# Board.net
KiCad netlist of a schematic drawn in EAGLE
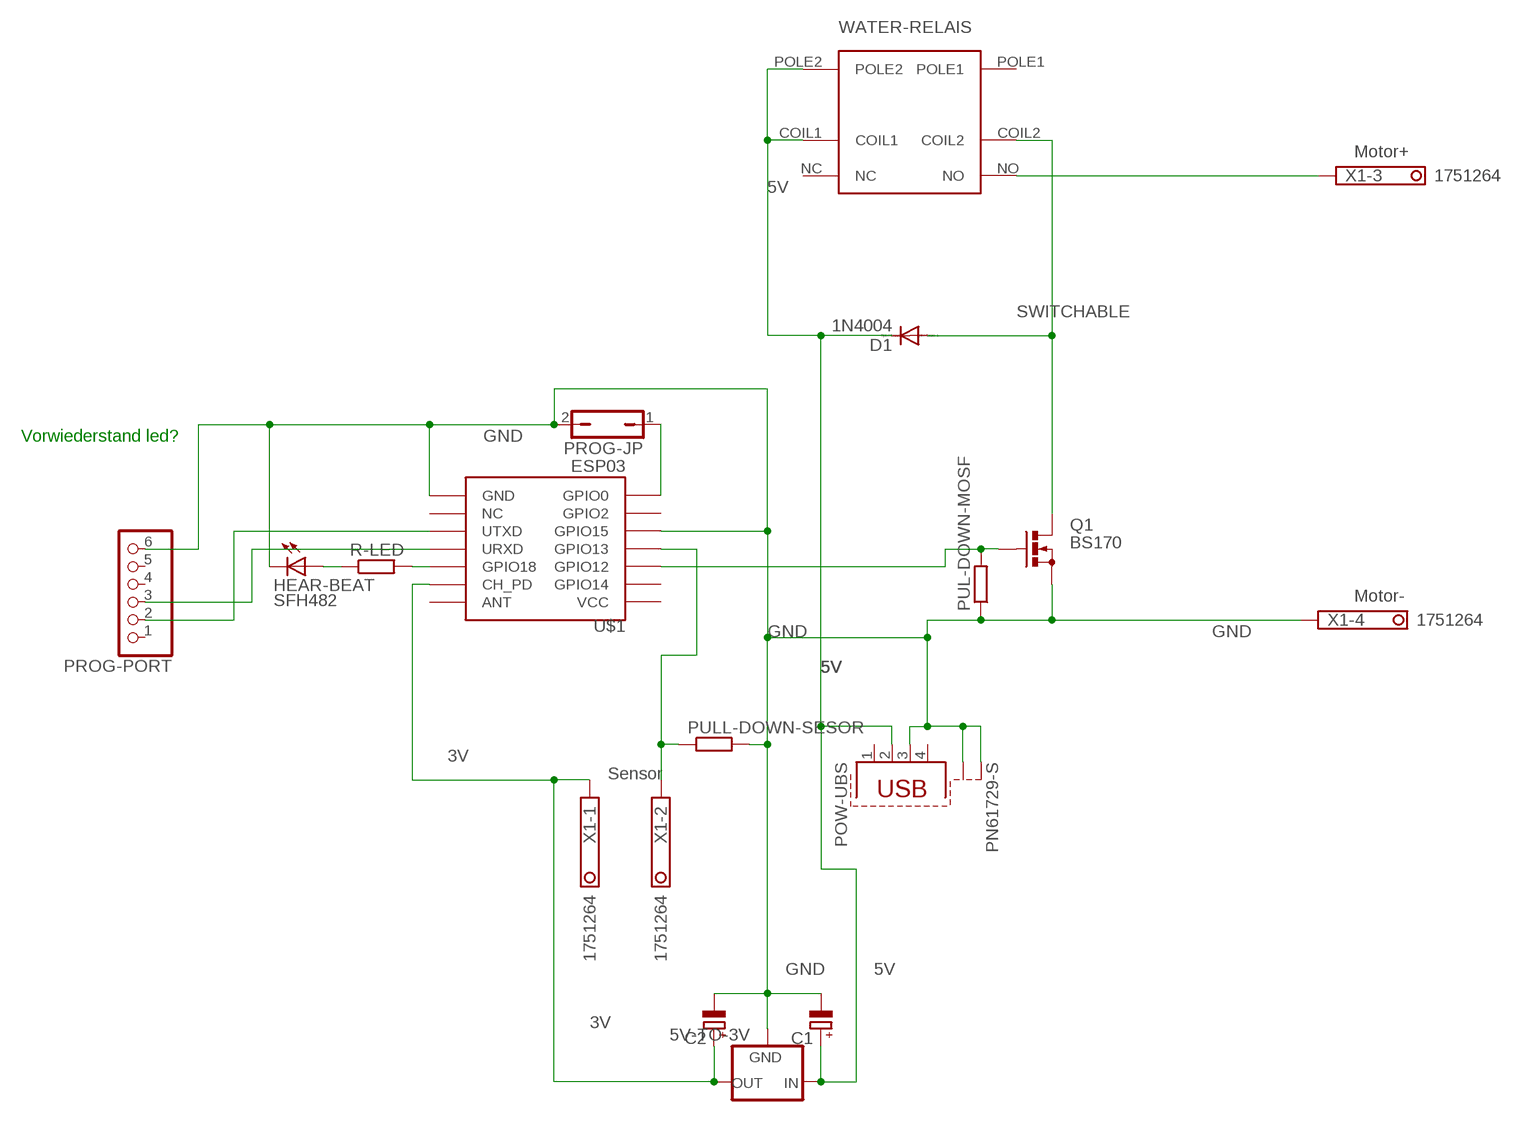
[diagram p0: schematic, sheet 1]

(export (version "E")
  (design (tool "Eeschema 10.0.6"))
  (components
    (comp (ref "5V-TO-3V")
      (value "78XXL")
      (footprint "eagle-import:78XXL")
      (libsource (lib "eagle-import") (part "78XXL"))
    )
    (comp (ref "C1")
      (value "CPOL-EUE2.5-6")
      (footprint "eagle-import:E2,5-6")
      (libsource (lib "eagle-import") (part "CPOL-EUE2.5-6"))
    )
    (comp (ref "C2")
      (value "CPOL-EUE2.5-6")
      (footprint "eagle-import:E2,5-6")
      (libsource (lib "eagle-import") (part "CPOL-EUE2.5-6"))
    )
    (comp (ref "D1")
      (value "1N4004")
      (footprint "eagle-import:DO41-10")
      (libsource (lib "eagle-import") (part "1N4004"))
    )
    (comp (ref "HEAR-BEAT")
      (value "SFH482")
      (footprint "eagle-import:SFH482")
      (libsource (lib "eagle-import") (part "SFH482"))
    )
    (comp (ref "POW-UBS")
      (value "PN61729-S")
      (footprint "eagle-import:PN61729-S")
      (libsource (lib "eagle-import") (part "PN61729-S"))
    )
    (comp (ref "PROG-JP")
      (value "JP1Q")
      (footprint "eagle-import:JP1")
      (libsource (lib "eagle-import") (part "JP1Q"))
    )
    (comp (ref "PROG-PORT")
      (value "PINHD-1X6")
      (footprint "eagle-import:1X06")
      (libsource (lib "eagle-import") (part "PINHD-1X6"))
    )
    (comp (ref "PUL-DOWN-MOSF")
      (value "R-EU_0207/10")
      (footprint "eagle-import:0207_10")
      (libsource (lib "eagle-import") (part "R-EU_0207/10"))
    )
    (comp (ref "PULL-DOWN-SESOR")
      (value "R-EU_0207/10")
      (footprint "eagle-import:0207_10")
      (libsource (lib "eagle-import") (part "R-EU_0207/10"))
    )
    (comp (ref "Q1")
      (value "BS170")
      (footprint "eagle-import:SOT54E")
      (libsource (lib "eagle-import") (part "BS170"))
    )
    (comp (ref "R-LED")
      (value "R-EU_0207/10")
      (footprint "eagle-import:0207_10")
      (libsource (lib "eagle-import") (part "R-EU_0207/10"))
    )
    (comp (ref "U$1")
      (value "ESP03")
      (footprint "eagle-import:ESP03")
      (libsource (lib "eagle-import") (part "ESP03"))
    )
    (comp (ref "WATER-RELAIS")
      (value "HJR-4102-L-C")
      (footprint "eagle-import:HJR-4102-L")
      (libsource (lib "eagle-import") (part "HJR-4102-L-C"))
    )
    (comp (ref "X1")
      (value "1751264")
      (footprint "eagle-import:1751264")
      (libsource (lib "eagle-import") (part "1751264"))
    )
  )
  (nets
    (net (code "1") (name "/3V") (class "Default")
      (node (ref "5V-TO-3V") (pin "OUT") (pinfunction "OUT_OUT") (pintype "passive"))
      (node (ref "C2") (pin "+") (pinfunction "+_+") (pintype "passive"))
      (node (ref "U$1") (pin "CH_PD") (pinfunction "CH_PD_CH_PD") (pintype "bidirectional"))
      (node (ref "X1") (pin "1") (pinfunction "K_1") (pintype "passive"))
    )
    (net (code "2") (name "/5V") (class "Default")
      (node (ref "5V-TO-3V") (pin "IN") (pinfunction "IN_IN") (pintype "input"))
      (node (ref "C1") (pin "+") (pinfunction "+_+") (pintype "passive"))
      (node (ref "D1") (pin "C") (pinfunction "C_C") (pintype "passive"))
      (node (ref "POW-UBS") (pin "2") (pinfunction "2_2") (pintype "passive"))
      (node (ref "WATER-RELAIS") (pin "COIL1") (pinfunction "COIL1_COIL1") (pintype "bidirectional"))
      (node (ref "WATER-RELAIS") (pin "POLE2") (pinfunction "POLE2_POLE2") (pintype "bidirectional"))
    )
    (net (code "3") (name "/GND") (class "Default")
      (node (ref "5V-TO-3V") (pin "GND") (pinfunction "GND_GND") (pintype "input"))
      (node (ref "C1") (pin "-") (pinfunction "-_-") (pintype "passive"))
      (node (ref "C2") (pin "-") (pinfunction "-_-") (pintype "passive"))
      (node (ref "HEAR-BEAT") (pin "K") (pinfunction "C_K") (pintype "passive"))
      (node (ref "POW-UBS") (pin "3") (pinfunction "3_3") (pintype "passive"))
      (node (ref "POW-UBS") (pin "S1") (pinfunction "S1_S1") (pintype "passive"))
      (node (ref "POW-UBS") (pin "S2") (pinfunction "S2_S2") (pintype "passive"))
      (node (ref "PROG-JP") (pin "2") (pinfunction "2_2") (pintype "passive"))
      (node (ref "PROG-PORT") (pin "6") (pinfunction "6_6") (pintype "passive"))
      (node (ref "PUL-DOWN-MOSF") (pin "1") (pinfunction "1_1") (pintype "passive"))
      (node (ref "PULL-DOWN-SESOR") (pin "2") (pinfunction "2_2") (pintype "passive"))
      (node (ref "Q1") (pin "S") (pinfunction "S_S") (pintype "passive"))
      (node (ref "U$1") (pin "GND") (pinfunction "GND_GND") (pintype "bidirectional"))
      (node (ref "U$1") (pin "GPIO15") (pinfunction "GPIO15_GPIO15") (pintype "bidirectional"))
      (node (ref "X1") (pin "4") (pinfunction "K_4") (pintype "passive"))
    )
    (net (code "4") (name "/SWITCHABLE") (class "Default")
      (node (ref "D1") (pin "A") (pinfunction "A_A") (pintype "passive"))
      (node (ref "Q1") (pin "D") (pinfunction "D_D") (pintype "passive"))
      (node (ref "WATER-RELAIS") (pin "COIL2") (pinfunction "COIL2_COIL2") (pintype "bidirectional"))
    )
    (net (code "5") (name "Net-(HEAR-BEAT-PadA)") (class "Default")
      (node (ref "HEAR-BEAT") (pin "A") (pinfunction "A_A") (pintype "passive"))
      (node (ref "R-LED") (pin "1") (pinfunction "1_1") (pintype "passive"))
    )
    (net (code "6") (name "Net-(PROG-JP-Pad1)") (class "Default")
      (node (ref "PROG-JP") (pin "1") (pinfunction "1_1") (pintype "passive"))
      (node (ref "U$1") (pin "GPIO0") (pinfunction "GPIO0_GPIO0") (pintype "bidirectional"))
    )
    (net (code "7") (name "Net-(PROG-PORT-Pad2)") (class "Default")
      (node (ref "PROG-PORT") (pin "2") (pinfunction "2_2") (pintype "passive"))
      (node (ref "U$1") (pin "UTXD") (pinfunction "UTXD_UTXD") (pintype "bidirectional"))
    )
    (net (code "8") (name "Net-(PROG-PORT-Pad3)") (class "Default")
      (node (ref "PROG-PORT") (pin "3") (pinfunction "3_3") (pintype "passive"))
      (node (ref "U$1") (pin "URXD") (pinfunction "URXD_URXD") (pintype "bidirectional"))
    )
    (net (code "9") (name "Net-(PUL-DOWN-MOSF-Pad2)") (class "Default")
      (node (ref "PUL-DOWN-MOSF") (pin "2") (pinfunction "2_2") (pintype "passive"))
      (node (ref "Q1") (pin "G") (pinfunction "G_G") (pintype "passive"))
      (node (ref "U$1") (pin "GPIO12") (pinfunction "GPIO12_GPIO12") (pintype "bidirectional"))
    )
    (net (code "10") (name "Net-(R-LED-Pad2)") (class "Default")
      (node (ref "R-LED") (pin "2") (pinfunction "2_2") (pintype "passive"))
      (node (ref "U$1") (pin "GPIO18") (pinfunction "GPIO18_GPIO18") (pintype "bidirectional"))
    )
    (net (code "11") (name "Net-(X1B-K)") (class "Default")
      (node (ref "PULL-DOWN-SESOR") (pin "1") (pinfunction "1_1") (pintype "passive"))
      (node (ref "U$1") (pin "GPIO13") (pinfunction "GPIO13_GPIO13") (pintype "bidirectional"))
      (node (ref "X1") (pin "2") (pinfunction "K_2") (pintype "passive"))
    )
    (net (code "12") (name "Net-(X1C-K)") (class "Default")
      (node (ref "WATER-RELAIS") (pin "NO") (pinfunction "NO_NO") (pintype "bidirectional"))
      (node (ref "X1") (pin "3") (pinfunction "K_3") (pintype "passive"))
    )
    (net (code "13") (name "unconnected-(POW-UBS-Pad1)") (class "Default")
      (node (ref "POW-UBS") (pin "1") (pinfunction "1_1") (pintype "passive"))
    )
    (net (code "14") (name "unconnected-(POW-UBS-Pad4)") (class "Default")
      (node (ref "POW-UBS") (pin "4") (pinfunction "4_4") (pintype "passive"))
    )
    (net (code "15") (name "unconnected-(PROG-PORT-Pad1)") (class "Default")
      (node (ref "PROG-PORT") (pin "1") (pinfunction "1_1") (pintype "passive"))
    )
    (net (code "16") (name "unconnected-(PROG-PORT-Pad4)") (class "Default")
      (node (ref "PROG-PORT") (pin "4") (pinfunction "4_4") (pintype "passive"))
    )
    (net (code "17") (name "unconnected-(PROG-PORT-Pad5)") (class "Default")
      (node (ref "PROG-PORT") (pin "5") (pinfunction "5_5") (pintype "passive"))
    )
    (net (code "18") (name "unconnected-(U$1-PadANT)") (class "Default")
      (node (ref "U$1") (pin "ANT") (pinfunction "ANT_ANT") (pintype "bidirectional"))
    )
    (net (code "19") (name "unconnected-(U$1-PadGPIO2)") (class "Default")
      (node (ref "U$1") (pin "GPIO2") (pinfunction "GPIO2_GPIO2") (pintype "bidirectional"))
    )
    (net (code "20") (name "unconnected-(U$1-PadGPIO14)") (class "Default")
      (node (ref "U$1") (pin "GPIO14") (pinfunction "GPIO14_GPIO14") (pintype "bidirectional"))
    )
    (net (code "21") (name "unconnected-(U$1-PadNC)") (class "Default")
      (node (ref "U$1") (pin "NC") (pinfunction "NC_NC") (pintype "bidirectional"))
    )
    (net (code "22") (name "unconnected-(U$1-PadVCC)") (class "Default")
      (node (ref "U$1") (pin "VCC") (pinfunction "VCC_VCC") (pintype "bidirectional"))
    )
    (net (code "23") (name "unconnected-(WATER-RELAIS-PadNC)") (class "Default")
      (node (ref "WATER-RELAIS") (pin "NC") (pinfunction "NC_NC") (pintype "bidirectional"))
    )
    (net (code "24") (name "unconnected-(WATER-RELAIS-PadPOLE1)") (class "Default")
      (node (ref "WATER-RELAIS") (pin "POLE1") (pinfunction "POLE1_POLE1") (pintype "bidirectional"))
    )
  )
)
